# CAN.net
KiCad netlist of a schematic drawn in Altium Designer
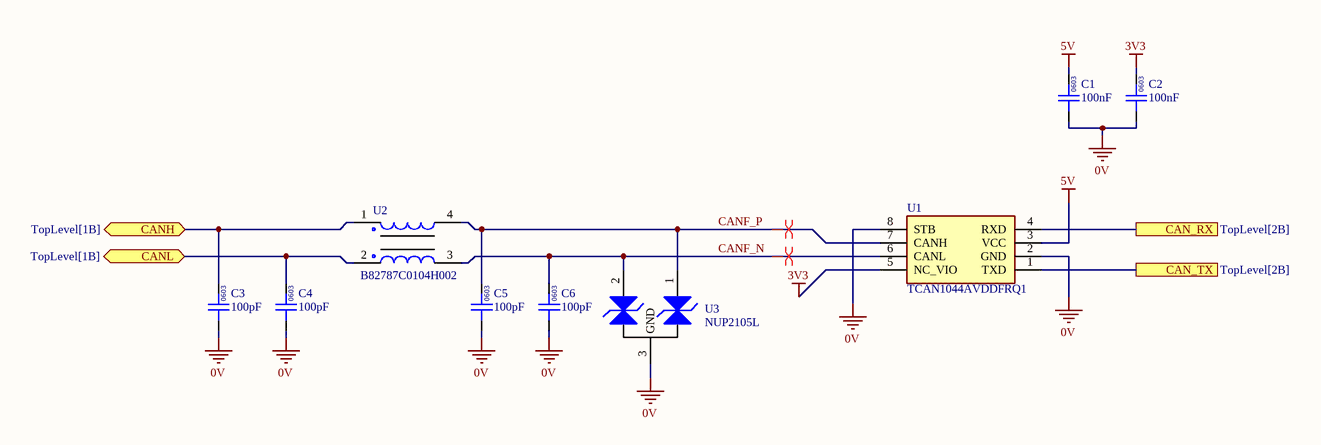
[diagram p0: CAN.SchDoc]

(export (version "E")
  (design (tool "Eeschema 10.0.6"))
  (components
    (comp (ref "C1")
      (value "100nF")
      (footprint "0603")
      (fields
        (field (name "PART NUMBER") "GCM188L81H104KA57D")
        (field (name "MANUFACTURER") "muRata")
        (field (name "TOLERANCE") "±10%")
      )
      (libsource (lib "ts_standard_library") (part "Capacitor 0603"))
    )
    (comp (ref "C2")
      (value "100nF")
      (footprint "0603")
      (fields
        (field (name "PART NUMBER") "GCM188L81H104KA57D")
        (field (name "MANUFACTURER") "muRata")
        (field (name "TOLERANCE") "±10%")
      )
      (libsource (lib "ts_standard_library") (part "Capacitor 0603"))
    )
    (comp (ref "C3")
      (value "100pF")
      (footprint "0603")
      (fields
        (field (name "PART NUMBER") "GRM1885C1H101JA01D")
        (field (name "MANUFACTURER") "Murata Electronics")
        (field (name "TOLERANCE") "±5%")
      )
      (libsource (lib "ts_standard_library") (part "Capacitor 0603"))
    )
    (comp (ref "C4")
      (value "100pF")
      (footprint "0603")
      (fields
        (field (name "PART NUMBER") "GRM1885C1H101JA01D")
        (field (name "MANUFACTURER") "Murata Electronics")
        (field (name "TOLERANCE") "±5%")
      )
      (libsource (lib "ts_standard_library") (part "Capacitor 0603"))
    )
    (comp (ref "C5")
      (value "100pF")
      (footprint "0603")
      (fields
        (field (name "PART NUMBER") "GRM1885C1H101JA01D")
        (field (name "MANUFACTURER") "Murata Electronics")
        (field (name "TOLERANCE") "±5%")
      )
      (libsource (lib "ts_standard_library") (part "Capacitor 0603"))
    )
    (comp (ref "C6")
      (value "100pF")
      (footprint "0603")
      (fields
        (field (name "PART NUMBER") "GRM1885C1H101JA01D")
        (field (name "MANUFACTURER") "Murata Electronics")
        (field (name "TOLERANCE") "±5%")
      )
      (libsource (lib "ts_standard_library") (part "Capacitor 0603"))
    )
    (comp (ref "U1")
      (value "TCAN1044AVDDFRQ1")
      (footprint "SamacSys:SOT65P280X110-8N")
      (description "Integrated Circuit")
      (fields (field (name "MOUSER PART NUMBER") "595-TCAN1044AVDDFRQ1"))
      (libsource (lib "*") (part "TCAN1044AVDDFRQ1"))
    )
    (comp (ref "U2")
      (value "B82787C0104H002")
      (footprint "TDK 4-PC Pad")
      (fields
        (field (name "MANUFACTURER") "EPCOS (TDK)")
        (field (name "DIGIKEY PART NUMBER") "495-4598-1-ND")
      )
      (libsource (lib "ts_standard_library") (part "B82787C0104H002"))
    )
    (comp (ref "U3")
      (value "NUP2105L")
      (footprint "ON SOT-23")
      (description "Dual Line CAN Bus Protector")
      (fields
        (field (name "MANUFACTURER") "ON Semiconductor")
        (field (name "DIGIKEY PART NUMBER") "NUP2105LT1GOSCT-ND")
      )
      (libsource (lib "ts_standard_library") (part "NUP2105L"))
    )
  )
  (nets
    (net (code "1") (name "/CANF_N") (class "Default")
      (node (ref "C6") (pin "2") (pinfunction "2_2") (pintype "passive"))
      (node (ref "U1") (pin "6") (pinfunction "CANL_6") (pintype "passive"))
      (node (ref "U2") (pin "3") (pinfunction "3_3") (pintype "passive"))
      (node (ref "U3") (pin "2") (pinfunction "CAN_L_2") (pintype "passive"))
    )
    (net (code "2") (name "/CANF_P") (class "Default")
      (node (ref "C5") (pin "2") (pinfunction "2_2") (pintype "passive"))
      (node (ref "U1") (pin "7") (pinfunction "CANH_7") (pintype "passive"))
      (node (ref "U2") (pin "4") (pinfunction "4_4") (pintype "passive"))
      (node (ref "U3") (pin "1") (pinfunction "CAN_H_1") (pintype "passive"))
    )
    (net (code "3") (name "/CANH") (class "Default")
      (node (ref "C3") (pin "2") (pinfunction "2_2") (pintype "passive"))
      (node (ref "U2") (pin "1") (pinfunction "1_1") (pintype "passive"))
    )
    (net (code "4") (name "/CANL") (class "Default")
      (node (ref "C4") (pin "2") (pinfunction "2_2") (pintype "passive"))
      (node (ref "U2") (pin "2") (pinfunction "2_2") (pintype "passive"))
    )
    (net (code "5") (name "/CAN_RX") (class "Default")
      (node (ref "U1") (pin "4") (pinfunction "RXD_4") (pintype "passive"))
    )
    (net (code "6") (name "/CAN_TX") (class "Default")
      (node (ref "U1") (pin "1") (pinfunction "TXD_1") (pintype "passive"))
    )
    (net (code "7") (name "0V") (class "Default")
      (node (ref "C1") (pin "1") (pinfunction "1_1") (pintype "passive"))
      (node (ref "C2") (pin "1") (pinfunction "1_1") (pintype "passive"))
      (node (ref "C3") (pin "1") (pinfunction "1_1") (pintype "passive"))
      (node (ref "C4") (pin "1") (pinfunction "1_1") (pintype "passive"))
      (node (ref "C5") (pin "1") (pinfunction "1_1") (pintype "passive"))
      (node (ref "C6") (pin "1") (pinfunction "1_1") (pintype "passive"))
      (node (ref "U1") (pin "2") (pinfunction "GND_2") (pintype "passive"))
      (node (ref "U1") (pin "8") (pinfunction "STB_8") (pintype "passive"))
      (node (ref "U3") (pin "3") (pinfunction "GND_3") (pintype "passive"))
    )
    (net (code "8") (name "3V3") (class "Default")
      (node (ref "C2") (pin "2") (pinfunction "2_2") (pintype "passive"))
      (node (ref "U1") (pin "5") (pinfunction "NC_VIO_5") (pintype "passive"))
    )
    (net (code "9") (name "5V") (class "Default")
      (node (ref "C1") (pin "2") (pinfunction "2_2") (pintype "passive"))
      (node (ref "U1") (pin "3") (pinfunction "VCC_3") (pintype "passive"))
    )
  )
)
